# core.net
KiCad netlist of a schematic drawn in Altium Designer
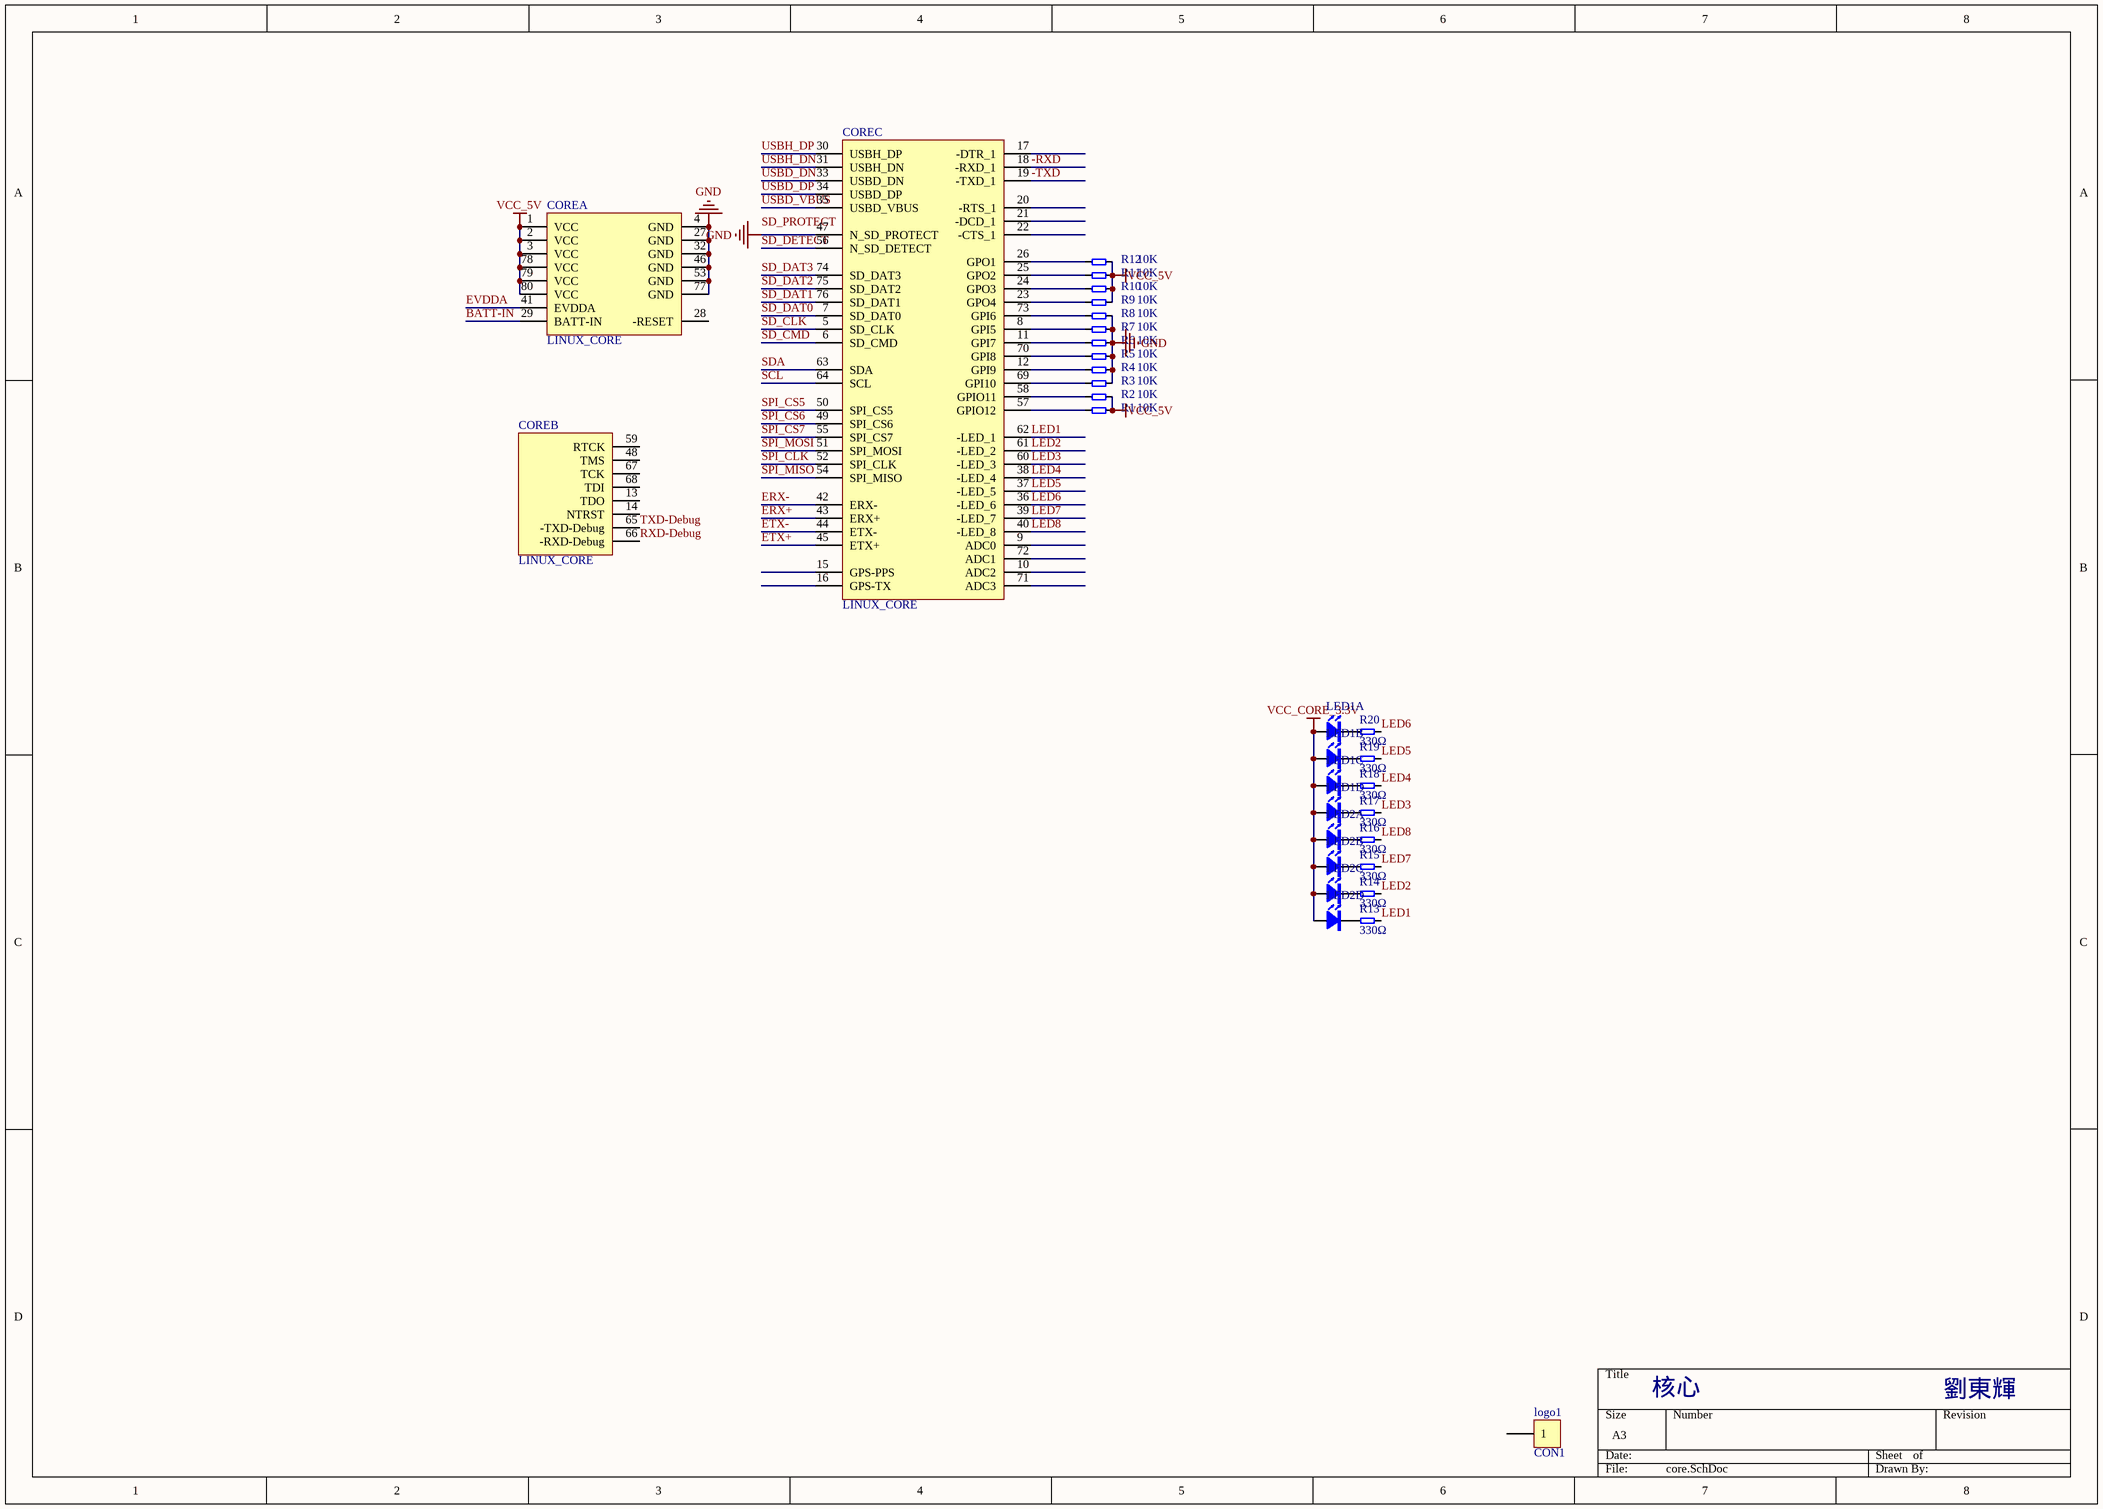
[diagram p0: core.SchDoc]

(export (version "E")
  (design (tool "Eeschema 10.0.6"))
  (components
    (comp (ref "CORE")
      (value "LINUX_CORE")
      (footprint "LINUX_CORE")
      (libsource (lib "Schlib1") (part "LINUX_CORE"))
    )
    (comp (ref "LED1")
      (value "~")
      (footprint "3MM-4SYG/S530-Z")
      (libsource (lib "Display") (part "3MM-4SYG/S530-Z"))
    )
    (comp (ref "LED2")
      (value "~")
      (footprint "3MM-4SYG/S530-Z")
      (libsource (lib "Display") (part "3MM-4SYG/S530-Z"))
    )
    (comp (ref "logo1")
      (value "CON1")
      (footprint "LIU")
      (description "Connector")
      (libsource (lib "接插件") (part "CON1"))
    )
    (comp (ref "R1")
      (value "10K")
      (footprint "0805/2012 R3")
      (description "Resistor")
      (libsource (lib "标准元件库") (part "RES2"))
    )
    (comp (ref "R2")
      (value "10K")
      (footprint "0805/2012 R3")
      (description "Resistor")
      (libsource (lib "标准元件库") (part "RES2"))
    )
    (comp (ref "R3")
      (value "10K")
      (footprint "0805/2012 R3")
      (description "Resistor")
      (libsource (lib "标准元件库") (part "RES2"))
    )
    (comp (ref "R4")
      (value "10K")
      (footprint "0805/2012 R3")
      (description "Resistor")
      (libsource (lib "标准元件库") (part "RES2"))
    )
    (comp (ref "R5")
      (value "10K")
      (footprint "0805/2012 R3")
      (description "Resistor")
      (libsource (lib "标准元件库") (part "RES2"))
    )
    (comp (ref "R6")
      (value "10K")
      (footprint "0805/2012 R3")
      (description "Resistor")
      (libsource (lib "标准元件库") (part "RES2"))
    )
    (comp (ref "R7")
      (value "10K")
      (footprint "0805/2012 R3")
      (description "Resistor")
      (libsource (lib "标准元件库") (part "RES2"))
    )
    (comp (ref "R8")
      (value "10K")
      (footprint "0805/2012 R3")
      (description "Resistor")
      (libsource (lib "标准元件库") (part "RES2"))
    )
    (comp (ref "R9")
      (value "10K")
      (footprint "0805/2012 R3")
      (description "Resistor")
      (libsource (lib "标准元件库") (part "RES2"))
    )
    (comp (ref "R10")
      (value "10K")
      (footprint "0805/2012 R3")
      (description "Resistor")
      (libsource (lib "标准元件库") (part "RES2"))
    )
    (comp (ref "R11")
      (value "10K")
      (footprint "0805/2012 R3")
      (description "Resistor")
      (libsource (lib "标准元件库") (part "RES2"))
    )
    (comp (ref "R12")
      (value "10K")
      (footprint "0805/2012 R3")
      (description "Resistor")
      (libsource (lib "标准元件库") (part "RES2"))
    )
    (comp (ref "R13")
      (value "330Ω")
      (footprint "0805/2012 R3")
      (description "Resistor")
      (libsource (lib "标准元件库") (part "RES2"))
    )
    (comp (ref "R14")
      (value "330Ω")
      (footprint "0805/2012 R3")
      (description "Resistor")
      (libsource (lib "标准元件库") (part "RES2"))
    )
    (comp (ref "R15")
      (value "330Ω")
      (footprint "0805/2012 R3")
      (description "Resistor")
      (libsource (lib "标准元件库") (part "RES2"))
    )
    (comp (ref "R16")
      (value "330Ω")
      (footprint "0805/2012 R3")
      (description "Resistor")
      (libsource (lib "标准元件库") (part "RES2"))
    )
    (comp (ref "R17")
      (value "330Ω")
      (footprint "0805/2012 R3")
      (description "Resistor")
      (libsource (lib "标准元件库") (part "RES2"))
    )
    (comp (ref "R18")
      (value "330Ω")
      (footprint "0805/2012 R3")
      (description "Resistor")
      (libsource (lib "标准元件库") (part "RES2"))
    )
    (comp (ref "R19")
      (value "330Ω")
      (footprint "0805/2012 R3")
      (description "Resistor")
      (libsource (lib "标准元件库") (part "RES2"))
    )
    (comp (ref "R20")
      (value "330Ω")
      (footprint "0805/2012 R3")
      (description "Resistor")
      (libsource (lib "标准元件库") (part "RES2"))
    )
  )
  (nets
    (net (code "1") (name "/-RXD") (class "Default")
      (node (ref "CORE") (pin "18") (pinfunction "-RXD_1_18") (pintype "passive"))
    )
    (net (code "2") (name "/-TXD") (class "Default")
      (node (ref "CORE") (pin "19") (pinfunction "-TXD_1_19") (pintype "passive"))
    )
    (net (code "3") (name "/BATT-IN") (class "Default")
      (node (ref "CORE") (pin "29") (pinfunction "BATT-IN_29") (pintype "passive"))
    )
    (net (code "4") (name "/ERX+") (class "Default")
      (node (ref "CORE") (pin "43") (pinfunction "ERX+_43") (pintype "passive"))
    )
    (net (code "5") (name "/ERX-") (class "Default")
      (node (ref "CORE") (pin "42") (pinfunction "ERX-_42") (pintype "passive"))
    )
    (net (code "6") (name "/ETX+") (class "Default")
      (node (ref "CORE") (pin "45") (pinfunction "ETX+_45") (pintype "passive"))
    )
    (net (code "7") (name "/ETX-") (class "Default")
      (node (ref "CORE") (pin "44") (pinfunction "ETX-_44") (pintype "passive"))
    )
    (net (code "8") (name "/EVDDA") (class "Default")
      (node (ref "CORE") (pin "41") (pinfunction "EVDDA_41") (pintype "passive"))
    )
    (net (code "9") (name "/LED1") (class "Default")
      (node (ref "CORE") (pin "62") (pinfunction "-LED_1_62") (pintype "passive"))
      (node (ref "R13") (pin "2") (pinfunction "2_2") (pintype "passive"))
    )
    (net (code "10") (name "/LED2") (class "Default")
      (node (ref "CORE") (pin "61") (pinfunction "-LED_2_61") (pintype "passive"))
      (node (ref "R14") (pin "2") (pinfunction "2_2") (pintype "passive"))
    )
    (net (code "11") (name "/LED3") (class "Default")
      (node (ref "CORE") (pin "60") (pinfunction "-LED_3_60") (pintype "passive"))
      (node (ref "R17") (pin "2") (pinfunction "2_2") (pintype "passive"))
    )
    (net (code "12") (name "/LED4") (class "Default")
      (node (ref "CORE") (pin "38") (pinfunction "-LED_4_38") (pintype "passive"))
      (node (ref "R18") (pin "2") (pinfunction "2_2") (pintype "passive"))
    )
    (net (code "13") (name "/LED5") (class "Default")
      (node (ref "CORE") (pin "37") (pinfunction "-LED_5_37") (pintype "passive"))
      (node (ref "R19") (pin "2") (pinfunction "2_2") (pintype "passive"))
    )
    (net (code "14") (name "/LED6") (class "Default")
      (node (ref "CORE") (pin "36") (pinfunction "-LED_6_36") (pintype "passive"))
      (node (ref "R20") (pin "2") (pinfunction "2_2") (pintype "passive"))
    )
    (net (code "15") (name "/LED7") (class "Default")
      (node (ref "CORE") (pin "39") (pinfunction "-LED_7_39") (pintype "passive"))
      (node (ref "R15") (pin "2") (pinfunction "2_2") (pintype "passive"))
    )
    (net (code "16") (name "/LED8") (class "Default")
      (node (ref "CORE") (pin "40") (pinfunction "-LED_8_40") (pintype "passive"))
      (node (ref "R16") (pin "2") (pinfunction "2_2") (pintype "passive"))
    )
    (net (code "17") (name "/RXD-Debug") (class "Default")
      (node (ref "CORE") (pin "66") (pinfunction "-RXD-Debug_66") (pintype "passive"))
    )
    (net (code "18") (name "/SCL") (class "Default")
      (node (ref "CORE") (pin "64") (pinfunction "SCL_64") (pintype "passive"))
    )
    (net (code "19") (name "/SDA") (class "Default")
      (node (ref "CORE") (pin "63") (pinfunction "SDA_63") (pintype "passive"))
    )
    (net (code "20") (name "/SD_CLK") (class "Default")
      (node (ref "CORE") (pin "5") (pinfunction "SD_CLK_5") (pintype "passive"))
    )
    (net (code "21") (name "/SD_CMD") (class "Default")
      (node (ref "CORE") (pin "6") (pinfunction "SD_CMD_6") (pintype "passive"))
    )
    (net (code "22") (name "/SD_DAT0") (class "Default")
      (node (ref "CORE") (pin "7") (pinfunction "SD_DAT0_7") (pintype "passive"))
    )
    (net (code "23") (name "/SD_DAT1") (class "Default")
      (node (ref "CORE") (pin "76") (pinfunction "SD_DAT1_76") (pintype "passive"))
    )
    (net (code "24") (name "/SD_DAT2") (class "Default")
      (node (ref "CORE") (pin "75") (pinfunction "SD_DAT2_75") (pintype "passive"))
    )
    (net (code "25") (name "/SD_DAT3") (class "Default")
      (node (ref "CORE") (pin "74") (pinfunction "SD_DAT3_74") (pintype "passive"))
    )
    (net (code "26") (name "/SD_DETECT") (class "Default")
      (node (ref "CORE") (pin "56") (pinfunction "N_SD_DETECT_56") (pintype "passive"))
    )
    (net (code "28") (name "/SPI_CLK") (class "Default")
      (node (ref "CORE") (pin "52") (pinfunction "SPI_CLK_52") (pintype "passive"))
    )
    (net (code "29") (name "/SPI_CS5") (class "Default")
      (node (ref "CORE") (pin "50") (pinfunction "SPI_CS5_50") (pintype "passive"))
    )
    (net (code "30") (name "/SPI_CS6") (class "Default")
      (node (ref "CORE") (pin "49") (pinfunction "SPI_CS6_49") (pintype "passive"))
    )
    (net (code "31") (name "/SPI_CS7") (class "Default")
      (node (ref "CORE") (pin "55") (pinfunction "SPI_CS7_55") (pintype "passive"))
    )
    (net (code "32") (name "/SPI_MISO") (class "Default")
      (node (ref "CORE") (pin "54") (pinfunction "SPI_MISO_54") (pintype "passive"))
    )
    (net (code "33") (name "/SPI_MOSI") (class "Default")
      (node (ref "CORE") (pin "51") (pinfunction "SPI_MOSI_51") (pintype "passive"))
    )
    (net (code "34") (name "/TXD-Debug") (class "Default")
      (node (ref "CORE") (pin "65") (pinfunction "-TXD-Debug_65") (pintype "passive"))
    )
    (net (code "35") (name "/USBD_DN") (class "Default")
      (node (ref "CORE") (pin "33") (pinfunction "USBD_DN_33") (pintype "passive"))
    )
    (net (code "36") (name "/USBD_DP") (class "Default")
      (node (ref "CORE") (pin "34") (pinfunction "USBD_DP_34") (pintype "passive"))
    )
    (net (code "37") (name "/USBD_VBUS") (class "Default")
      (node (ref "CORE") (pin "35") (pinfunction "USBD_VBUS_35") (pintype "passive"))
    )
    (net (code "38") (name "/USBH_DN") (class "Default")
      (node (ref "CORE") (pin "31") (pinfunction "USBH_DN_31") (pintype "passive"))
    )
    (net (code "39") (name "/USBH_DP") (class "Default")
      (node (ref "CORE") (pin "30") (pinfunction "USBH_DP_30") (pintype "passive"))
    )
    (net (code "40") (name "GND") (class "Default")
      (node (ref "CORE") (pin "27") (pinfunction "GND_27") (pintype "passive"))
      (node (ref "CORE") (pin "32") (pinfunction "GND_32") (pintype "passive"))
      (node (ref "CORE") (pin "4") (pinfunction "GND_4") (pintype "passive"))
      (node (ref "CORE") (pin "46") (pinfunction "GND_46") (pintype "passive"))
      (node (ref "CORE") (pin "47") (pinfunction "N_SD_PROTECT_47") (pintype "passive"))
      (node (ref "CORE") (pin "53") (pinfunction "GND_53") (pintype "passive"))
      (node (ref "CORE") (pin "77") (pinfunction "GND_77") (pintype "passive"))
      (node (ref "R3") (pin "2") (pinfunction "2_2") (pintype "passive"))
      (node (ref "R4") (pin "2") (pinfunction "2_2") (pintype "passive"))
      (node (ref "R5") (pin "2") (pinfunction "2_2") (pintype "passive"))
      (node (ref "R6") (pin "2") (pinfunction "2_2") (pintype "passive"))
      (node (ref "R7") (pin "2") (pinfunction "2_2") (pintype "passive"))
      (node (ref "R8") (pin "2") (pinfunction "2_2") (pintype "passive"))
    )
    (net (code "41") (name "Net-(COREC-GPI5)") (class "Default")
      (node (ref "CORE") (pin "8") (pinfunction "GPI5_8") (pintype "passive"))
      (node (ref "R7") (pin "1") (pinfunction "1_1") (pintype "passive"))
    )
    (net (code "42") (name "Net-(COREC-GPI6)") (class "Default")
      (node (ref "CORE") (pin "73") (pinfunction "GPI6_73") (pintype "passive"))
      (node (ref "R8") (pin "1") (pinfunction "1_1") (pintype "passive"))
    )
    (net (code "43") (name "Net-(COREC-GPI7)") (class "Default")
      (node (ref "CORE") (pin "11") (pinfunction "GPI7_11") (pintype "passive"))
      (node (ref "R6") (pin "1") (pinfunction "1_1") (pintype "passive"))
    )
    (net (code "44") (name "Net-(COREC-GPI8)") (class "Default")
      (node (ref "CORE") (pin "70") (pinfunction "GPI8_70") (pintype "passive"))
      (node (ref "R5") (pin "1") (pinfunction "1_1") (pintype "passive"))
    )
    (net (code "45") (name "Net-(COREC-GPI9)") (class "Default")
      (node (ref "CORE") (pin "12") (pinfunction "GPI9_12") (pintype "passive"))
      (node (ref "R4") (pin "1") (pinfunction "1_1") (pintype "passive"))
    )
    (net (code "46") (name "Net-(COREC-GPI10)") (class "Default")
      (node (ref "CORE") (pin "69") (pinfunction "GPI10_69") (pintype "passive"))
      (node (ref "R3") (pin "1") (pinfunction "1_1") (pintype "passive"))
    )
    (net (code "47") (name "Net-(COREC-GPIO11)") (class "Default")
      (node (ref "CORE") (pin "58") (pinfunction "GPIO11_58") (pintype "passive"))
      (node (ref "R2") (pin "1") (pinfunction "1_1") (pintype "passive"))
    )
    (net (code "48") (name "Net-(COREC-GPIO12)") (class "Default")
      (node (ref "CORE") (pin "57") (pinfunction "GPIO12_57") (pintype "passive"))
      (node (ref "R1") (pin "1") (pinfunction "1_1") (pintype "passive"))
    )
    (net (code "49") (name "Net-(COREC-GPO1)") (class "Default")
      (node (ref "CORE") (pin "26") (pinfunction "GPO1_26") (pintype "passive"))
      (node (ref "R12") (pin "1") (pinfunction "1_1") (pintype "passive"))
    )
    (net (code "50") (name "Net-(COREC-GPO2)") (class "Default")
      (node (ref "CORE") (pin "25") (pinfunction "GPO2_25") (pintype "passive"))
      (node (ref "R11") (pin "1") (pinfunction "1_1") (pintype "passive"))
    )
    (net (code "51") (name "Net-(COREC-GPO3)") (class "Default")
      (node (ref "CORE") (pin "24") (pinfunction "GPO3_24") (pintype "passive"))
      (node (ref "R10") (pin "1") (pinfunction "1_1") (pintype "passive"))
    )
    (net (code "52") (name "Net-(COREC-GPO4)") (class "Default")
      (node (ref "CORE") (pin "23") (pinfunction "GPO4_23") (pintype "passive"))
      (node (ref "R9") (pin "1") (pinfunction "1_1") (pintype "passive"))
    )
    (net (code "53") (name "Net-(LED1A-1K)") (class "Default")
      (node (ref "LED1") (pin "2") (pinfunction "1K_2") (pintype "passive"))
      (node (ref "R20") (pin "1") (pinfunction "1_1") (pintype "passive"))
    )
    (net (code "54") (name "Net-(LED1B-2K)") (class "Default")
      (node (ref "LED1") (pin "4") (pinfunction "2K_4") (pintype "passive"))
      (node (ref "R19") (pin "1") (pinfunction "1_1") (pintype "passive"))
    )
    (net (code "55") (name "Net-(LED1C-3K)") (class "Default")
      (node (ref "LED1") (pin "6") (pinfunction "3K_6") (pintype "passive"))
      (node (ref "R18") (pin "1") (pinfunction "1_1") (pintype "passive"))
    )
    (net (code "56") (name "Net-(LED1D-4K)") (class "Default")
      (node (ref "LED1") (pin "8") (pinfunction "4K_8") (pintype "passive"))
      (node (ref "R17") (pin "1") (pinfunction "1_1") (pintype "passive"))
    )
    (net (code "57") (name "Net-(LED2A-1K)") (class "Default")
      (node (ref "LED2") (pin "2") (pinfunction "1K_2") (pintype "passive"))
      (node (ref "R16") (pin "1") (pinfunction "1_1") (pintype "passive"))
    )
    (net (code "58") (name "Net-(LED2B-2K)") (class "Default")
      (node (ref "LED2") (pin "4") (pinfunction "2K_4") (pintype "passive"))
      (node (ref "R15") (pin "1") (pinfunction "1_1") (pintype "passive"))
    )
    (net (code "59") (name "Net-(LED2C-3K)") (class "Default")
      (node (ref "LED2") (pin "6") (pinfunction "3K_6") (pintype "passive"))
      (node (ref "R14") (pin "1") (pinfunction "1_1") (pintype "passive"))
    )
    (net (code "60") (name "Net-(LED2D-4K)") (class "Default")
      (node (ref "LED2") (pin "8") (pinfunction "4K_8") (pintype "passive"))
      (node (ref "R13") (pin "1") (pinfunction "1_1") (pintype "passive"))
    )
    (net (code "61") (name "VCC_5V") (class "Default")
      (node (ref "CORE") (pin "1") (pinfunction "VCC_1") (pintype "passive"))
      (node (ref "CORE") (pin "2") (pinfunction "VCC_2") (pintype "passive"))
      (node (ref "CORE") (pin "3") (pinfunction "VCC_3") (pintype "passive"))
      (node (ref "CORE") (pin "78") (pinfunction "VCC_78") (pintype "passive"))
      (node (ref "CORE") (pin "79") (pinfunction "VCC_79") (pintype "passive"))
      (node (ref "CORE") (pin "80") (pinfunction "VCC_80") (pintype "passive"))
      (node (ref "R1") (pin "2") (pinfunction "2_2") (pintype "passive"))
      (node (ref "R10") (pin "2") (pinfunction "2_2") (pintype "passive"))
      (node (ref "R11") (pin "2") (pinfunction "2_2") (pintype "passive"))
      (node (ref "R12") (pin "2") (pinfunction "2_2") (pintype "passive"))
      (node (ref "R2") (pin "2") (pinfunction "2_2") (pintype "passive"))
      (node (ref "R9") (pin "2") (pinfunction "2_2") (pintype "passive"))
    )
    (net (code "62") (name "VCC_CORE_3.3V") (class "Default")
      (node (ref "LED1") (pin "1") (pinfunction "1A_1") (pintype "passive"))
      (node (ref "LED1") (pin "3") (pinfunction "2A_3") (pintype "passive"))
      (node (ref "LED1") (pin "5") (pinfunction "3A_5") (pintype "passive"))
      (node (ref "LED1") (pin "7") (pinfunction "4A_7") (pintype "passive"))
      (node (ref "LED2") (pin "1") (pinfunction "1A_1") (pintype "passive"))
      (node (ref "LED2") (pin "3") (pinfunction "2A_3") (pintype "passive"))
      (node (ref "LED2") (pin "5") (pinfunction "3A_5") (pintype "passive"))
      (node (ref "LED2") (pin "7") (pinfunction "4A_7") (pintype "passive"))
    )
    (net (code "63") (name "unconnected-(COREA--RESET-Pad28)") (class "Default")
      (node (ref "CORE") (pin "28") (pinfunction "-RESET_28") (pintype "passive"))
    )
    (net (code "64") (name "unconnected-(COREB-NTRST-Pad14)") (class "Default")
      (node (ref "CORE") (pin "14") (pinfunction "NTRST_14") (pintype "passive"))
    )
    (net (code "65") (name "unconnected-(COREB-RTCK-Pad59)") (class "Default")
      (node (ref "CORE") (pin "59") (pinfunction "RTCK_59") (pintype "passive"))
    )
    (net (code "66") (name "unconnected-(COREB-TCK-Pad67)") (class "Default")
      (node (ref "CORE") (pin "67") (pinfunction "TCK_67") (pintype "passive"))
    )
    (net (code "67") (name "unconnected-(COREB-TDI-Pad68)") (class "Default")
      (node (ref "CORE") (pin "68") (pinfunction "TDI_68") (pintype "passive"))
    )
    (net (code "68") (name "unconnected-(COREB-TDO-Pad13)") (class "Default")
      (node (ref "CORE") (pin "13") (pinfunction "TDO_13") (pintype "passive"))
    )
    (net (code "69") (name "unconnected-(COREB-TMS-Pad48)") (class "Default")
      (node (ref "CORE") (pin "48") (pinfunction "TMS_48") (pintype "passive"))
    )
    (net (code "70") (name "unconnected-(COREC--CTS_1-Pad22)") (class "Default")
      (node (ref "CORE") (pin "22") (pinfunction "-CTS_1_22") (pintype "passive"))
    )
    (net (code "71") (name "unconnected-(COREC--DCD_1-Pad21)") (class "Default")
      (node (ref "CORE") (pin "21") (pinfunction "-DCD_1_21") (pintype "passive"))
    )
    (net (code "72") (name "unconnected-(COREC--DTR_1-Pad17)") (class "Default")
      (node (ref "CORE") (pin "17") (pinfunction "-DTR_1_17") (pintype "passive"))
    )
    (net (code "73") (name "unconnected-(COREC--RTS_1-Pad20)") (class "Default")
      (node (ref "CORE") (pin "20") (pinfunction "-RTS_1_20") (pintype "passive"))
    )
    (net (code "74") (name "unconnected-(COREC-ADC0-Pad9)") (class "Default")
      (node (ref "CORE") (pin "9") (pinfunction "ADC0_9") (pintype "passive"))
    )
    (net (code "75") (name "unconnected-(COREC-ADC1-Pad72)") (class "Default")
      (node (ref "CORE") (pin "72") (pinfunction "ADC1_72") (pintype "passive"))
    )
    (net (code "76") (name "unconnected-(COREC-ADC2-Pad10)") (class "Default")
      (node (ref "CORE") (pin "10") (pinfunction "ADC2_10") (pintype "passive"))
    )
    (net (code "77") (name "unconnected-(COREC-ADC3-Pad71)") (class "Default")
      (node (ref "CORE") (pin "71") (pinfunction "ADC3_71") (pintype "passive"))
    )
    (net (code "78") (name "unconnected-(COREC-GPS-PPS-Pad15)") (class "Default")
      (node (ref "CORE") (pin "15") (pinfunction "GPS-PPS_15") (pintype "passive"))
    )
    (net (code "79") (name "unconnected-(COREC-GPS-TX-Pad16)") (class "Default")
      (node (ref "CORE") (pin "16") (pinfunction "GPS-TX_16") (pintype "passive"))
    )
    (net (code "80") (name "unconnected-(logo1-Pad1)") (class "Default")
      (node (ref "logo1") (pin "1") (pinfunction "1_1") (pintype "passive"))
    )
  )
)
